# control_v1.net
KiCad netlist of a schematic drawn in EAGLE
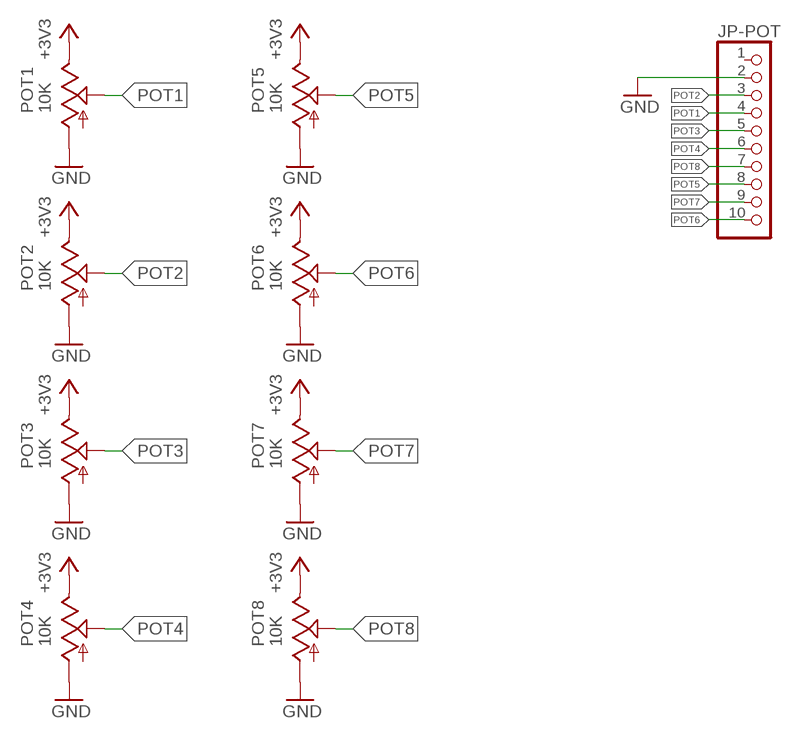
[diagram p0: schematic, sheet 1]
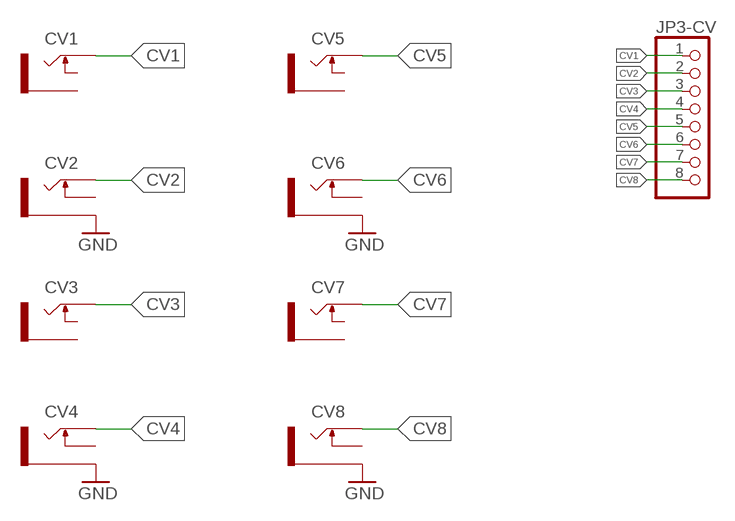
[diagram p1: schematic, sheet 2]
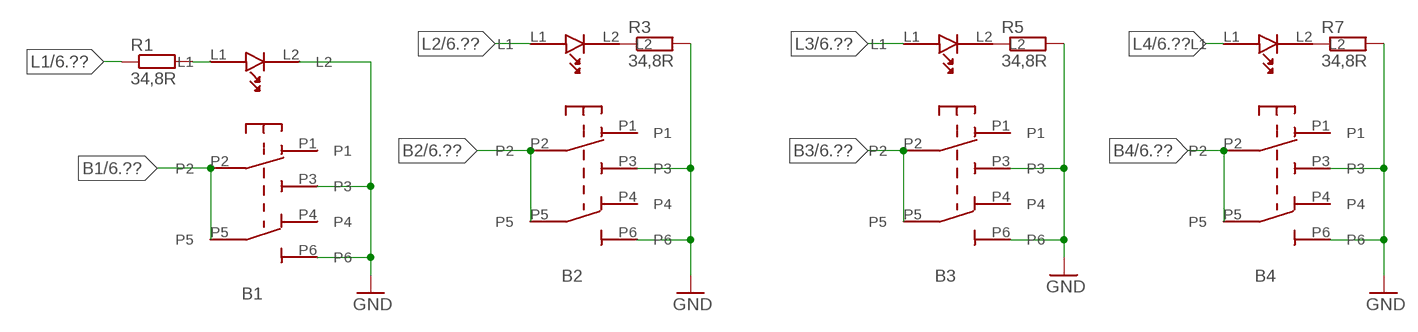
[diagram p2: schematic, sheet 3]
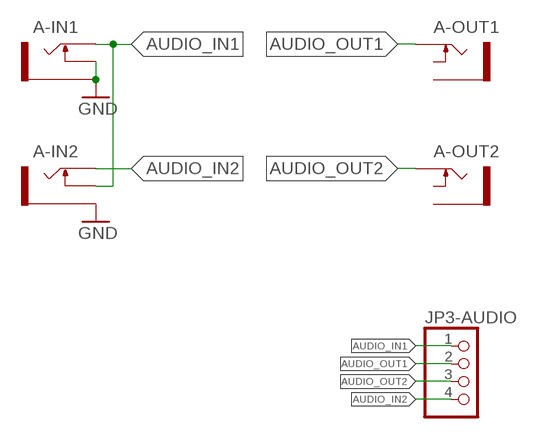
[diagram p3: schematic, sheet 4]
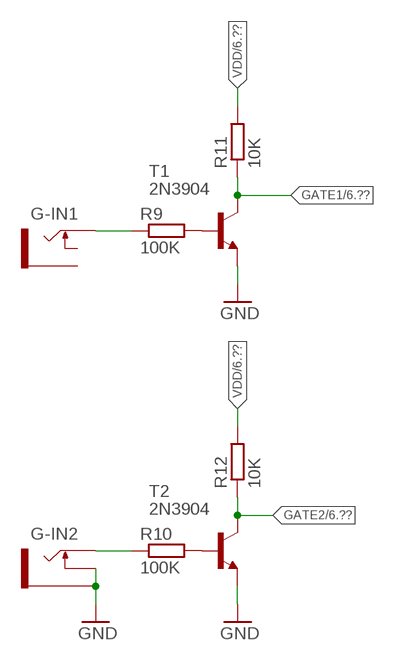
[diagram p4: schematic, sheet 5]
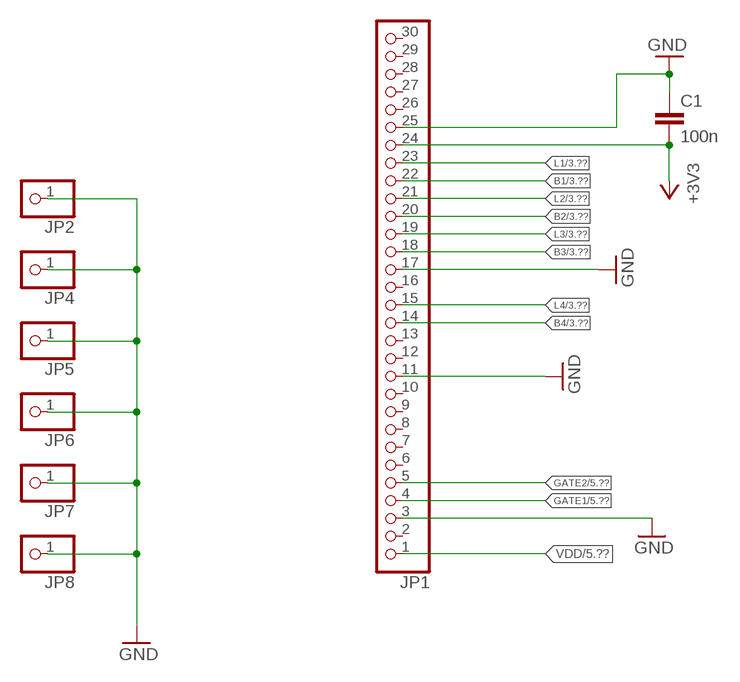
[diagram p5: schematic, sheet 6]

(export (version "E")
  (design (tool "Eeschema 10.0.6"))
  (components
    (comp (ref "JP-POT")
      (value "PINHD-1X10_2.54")
      (footprint "eagle-import:1X10")
      (libsource (lib "eagle-import") (part "PINHD-1X10_2.54"))
    )
    (comp (ref "POT1")
      (value "10K")
      (footprint "eagle-import:9MM_SNAP-IN_POT")
      (libsource (lib "eagle-import") (part "9MM_SNAP-IN_POT_"))
    )
    (comp (ref "POT2")
      (value "10K")
      (footprint "eagle-import:9MM_SNAP-IN_POT")
      (libsource (lib "eagle-import") (part "9MM_SNAP-IN_POT_"))
    )
    (comp (ref "POT3")
      (value "10K")
      (footprint "eagle-import:9MM_SNAP-IN_POT")
      (libsource (lib "eagle-import") (part "9MM_SNAP-IN_POT_"))
    )
    (comp (ref "POT4")
      (value "10K")
      (footprint "eagle-import:9MM_SNAP-IN_POT")
      (libsource (lib "eagle-import") (part "9MM_SNAP-IN_POT_"))
    )
    (comp (ref "POT5")
      (value "10K")
      (footprint "eagle-import:9MM_SNAP-IN_POT")
      (libsource (lib "eagle-import") (part "9MM_SNAP-IN_POT_"))
    )
    (comp (ref "POT6")
      (value "10K")
      (footprint "eagle-import:9MM_SNAP-IN_POT")
      (libsource (lib "eagle-import") (part "9MM_SNAP-IN_POT_"))
    )
    (comp (ref "POT7")
      (value "10K")
      (footprint "eagle-import:9MM_SNAP-IN_POT")
      (libsource (lib "eagle-import") (part "9MM_SNAP-IN_POT_"))
    )
    (comp (ref "POT8")
      (value "10K")
      (footprint "eagle-import:9MM_SNAP-IN_POT")
      (libsource (lib "eagle-import") (part "9MM_SNAP-IN_POT_"))
    )
    (comp (ref "A-IN1")
      (value "THONKICONNNEW")
      (footprint "eagle-import:WQP-PJ301M-12_JACK")
      (libsource (lib "eagle-import") (part "THONKICONNNEW"))
    )
    (comp (ref "A-IN2")
      (value "THONKICONNNEW")
      (footprint "eagle-import:WQP-PJ301M-12_JACK")
      (libsource (lib "eagle-import") (part "THONKICONNNEW"))
    )
    (comp (ref "A-OUT1")
      (value "THONKICONNNEW")
      (footprint "eagle-import:WQP-PJ301M-12_JACK")
      (libsource (lib "eagle-import") (part "MusicThingModular mod_THONKICONNNEW"))
    )
    (comp (ref "A-OUT2")
      (value "THONKICONNNEW")
      (footprint "eagle-import:WQP-PJ301M-12_JACK")
      (libsource (lib "eagle-import") (part "MusicThingModular mod_THONKICONNNEW"))
    )
    (comp (ref "JP3-AUDIO")
      (value "PINHD-1X4")
      (footprint "eagle-import:1X04")
      (libsource (lib "eagle-import") (part "PINHD-1X4"))
    )
    (comp (ref "C1")
      (value "100n")
      (footprint "eagle-import:C025-025X050")
      (libsource (lib "eagle-import") (part "C-EU025-025X050"))
    )
    (comp (ref "JP1")
      (value "PINHD-1X30")
      (footprint "eagle-import:1X30")
      (libsource (lib "eagle-import") (part "PINHD-1X30"))
    )
    (comp (ref "JP2")
      (value "PINHD-1X1")
      (footprint "eagle-import:1X01")
      (libsource (lib "eagle-import") (part "PINHD-1X1"))
    )
    (comp (ref "JP4")
      (value "PINHD-1X1")
      (footprint "eagle-import:1X01")
      (libsource (lib "eagle-import") (part "PINHD-1X1"))
    )
    (comp (ref "JP5")
      (value "PINHD-1X1")
      (footprint "eagle-import:1X01")
      (libsource (lib "eagle-import") (part "PINHD-1X1"))
    )
    (comp (ref "JP6")
      (value "PINHD-1X1")
      (footprint "eagle-import:1X01")
      (libsource (lib "eagle-import") (part "PINHD-1X1"))
    )
    (comp (ref "JP7")
      (value "PINHD-1X1")
      (footprint "eagle-import:1X01")
      (libsource (lib "eagle-import") (part "PINHD-1X1"))
    )
    (comp (ref "JP8")
      (value "PINHD-1X1")
      (footprint "eagle-import:1X01")
      (libsource (lib "eagle-import") (part "PINHD-1X1"))
    )
    (comp (ref "B1")
      (value "LP4OA1PBCTG")
      (footprint "eagle-import:LP4OA1PBCT")
      (libsource (lib "eagle-import") (part "LP4OA1PBCTG"))
    )
    (comp (ref "B2")
      (value "LP4OA1PBCTG")
      (footprint "eagle-import:LP4OA1PBCT")
      (libsource (lib "eagle-import") (part "LP4OA1PBCTG"))
    )
    (comp (ref "B3")
      (value "LP4OA1PBCTG")
      (footprint "eagle-import:LP4OA1PBCT")
      (libsource (lib "eagle-import") (part "LP4OA1PBCTG"))
    )
    (comp (ref "B4")
      (value "LP4OA1PBCTG")
      (footprint "eagle-import:LP4OA1PBCT")
      (libsource (lib "eagle-import") (part "LP4OA1PBCTG"))
    )
    (comp (ref "R1")
      (value "34,8R")
      (footprint "eagle-import:0207_7")
      (libsource (lib "eagle-import") (part "R-EU_0207/7"))
    )
    (comp (ref "R3")
      (value "34,8R")
      (footprint "eagle-import:0207_7")
      (libsource (lib "eagle-import") (part "R-EU_0207/7"))
    )
    (comp (ref "R5")
      (value "34,8R")
      (footprint "eagle-import:0207_7")
      (libsource (lib "eagle-import") (part "R-EU_0207/7"))
    )
    (comp (ref "R7")
      (value "34,8R")
      (footprint "eagle-import:0207_7")
      (libsource (lib "eagle-import") (part "R-EU_0207/7"))
    )
    (comp (ref "CV1")
      (value "THONKICONNNEW")
      (footprint "eagle-import:WQP-PJ301M-12_JACK")
      (libsource (lib "eagle-import") (part "MusicThingModular mod_THONKICONNNEW"))
    )
    (comp (ref "CV2")
      (value "THONKICONNNEW")
      (footprint "eagle-import:WQP-PJ301M-12_JACK")
      (libsource (lib "eagle-import") (part "THONKICONNNEW"))
    )
    (comp (ref "CV3")
      (value "THONKICONNNEW")
      (footprint "eagle-import:WQP-PJ301M-12_JACK")
      (libsource (lib "eagle-import") (part "MusicThingModular mod_THONKICONNNEW"))
    )
    (comp (ref "CV4")
      (value "THONKICONNNEW")
      (footprint "eagle-import:WQP-PJ301M-12_JACK")
      (libsource (lib "eagle-import") (part "THONKICONNNEW"))
    )
    (comp (ref "CV5")
      (value "THONKICONNNEW")
      (footprint "eagle-import:WQP-PJ301M-12_JACK")
      (libsource (lib "eagle-import") (part "MusicThingModular mod_THONKICONNNEW"))
    )
    (comp (ref "CV6")
      (value "THONKICONNNEW")
      (footprint "eagle-import:WQP-PJ301M-12_JACK")
      (libsource (lib "eagle-import") (part "THONKICONNNEW"))
    )
    (comp (ref "CV7")
      (value "THONKICONNNEW")
      (footprint "eagle-import:WQP-PJ301M-12_JACK")
      (libsource (lib "eagle-import") (part "MusicThingModular mod_THONKICONNNEW"))
    )
    (comp (ref "CV8")
      (value "THONKICONNNEW")
      (footprint "eagle-import:WQP-PJ301M-12_JACK")
      (libsource (lib "eagle-import") (part "THONKICONNNEW"))
    )
    (comp (ref "JP3-CV")
      (value "PINHD-1X8")
      (footprint "eagle-import:1X08")
      (libsource (lib "eagle-import") (part "PINHD-1X8"))
    )
    (comp (ref "G-IN1")
      (value "THONKICONNNEW")
      (footprint "eagle-import:WQP-PJ301M-12_JACK")
      (libsource (lib "eagle-import") (part "MusicThingModular mod_THONKICONNNEW"))
    )
    (comp (ref "G-IN2")
      (value "THONKICONNNEW")
      (footprint "eagle-import:WQP-PJ301M-12_JACK")
      (libsource (lib "eagle-import") (part "THONKICONNNEW"))
    )
    (comp (ref "R9")
      (value "100K")
      (footprint "eagle-import:0207_7")
      (libsource (lib "eagle-import") (part "R-EU_0207/7"))
    )
    (comp (ref "R10")
      (value "100K")
      (footprint "eagle-import:0207_7")
      (libsource (lib "eagle-import") (part "R-EU_0207/7"))
    )
    (comp (ref "R11")
      (value "10K")
      (footprint "eagle-import:0207_7")
      (libsource (lib "eagle-import") (part "R-EU_0207/7"))
    )
    (comp (ref "R12")
      (value "10K")
      (footprint "eagle-import:0207_7")
      (libsource (lib "eagle-import") (part "R-EU_0207/7"))
    )
    (comp (ref "T1")
      (value "2N3904")
      (footprint "eagle-import:TO92")
      (libsource (lib "eagle-import") (part "2N3904"))
    )
    (comp (ref "T2")
      (value "2N3904")
      (footprint "eagle-import:TO92")
      (libsource (lib "eagle-import") (part "2N3904"))
    )
  )
  (nets
    (net (code "1") (name "+3V3") (class "Default")
      (node (ref "C1") (pin "2") (pinfunction "2_2") (pintype "passive"))
      (node (ref "JP1") (pin "24") (pinfunction "24_24") (pintype "passive"))
      (node (ref "POT1") (pin "3") (pinfunction "E_3") (pintype "passive"))
      (node (ref "POT2") (pin "3") (pinfunction "E_3") (pintype "passive"))
      (node (ref "POT3") (pin "3") (pinfunction "E_3") (pintype "passive"))
      (node (ref "POT4") (pin "3") (pinfunction "E_3") (pintype "passive"))
      (node (ref "POT5") (pin "3") (pinfunction "E_3") (pintype "passive"))
      (node (ref "POT6") (pin "3") (pinfunction "E_3") (pintype "passive"))
      (node (ref "POT7") (pin "3") (pinfunction "E_3") (pintype "passive"))
      (node (ref "POT8") (pin "3") (pinfunction "E_3") (pintype "passive"))
    )
    (net (code "2") (name "AUDIO_IN1") (class "Default")
      (node (ref "A-IN1") (pin "P$1_TIP") (pinfunction "TIP_P$1_TIP") (pintype "passive"))
      (node (ref "A-IN2") (pin "P$2_SWITCH") (pinfunction "SWITCH_P$2_SWITCH") (pintype "passive"))
      (node (ref "JP3-AUDIO") (pin "1") (pinfunction "1_1") (pintype "passive"))
    )
    (net (code "3") (name "AUDIO_IN2") (class "Default")
      (node (ref "A-IN2") (pin "P$1_TIP") (pinfunction "TIP_P$1_TIP") (pintype "passive"))
      (node (ref "JP3-AUDIO") (pin "4") (pinfunction "4_4") (pintype "passive"))
    )
    (net (code "4") (name "AUDIO_OUT1") (class "Default")
      (node (ref "A-OUT1") (pin "P$1_TIP") (pinfunction "TIP_P$1_TIP") (pintype "passive"))
      (node (ref "JP3-AUDIO") (pin "2") (pinfunction "2_2") (pintype "passive"))
    )
    (net (code "5") (name "AUDIO_OUT2") (class "Default")
      (node (ref "A-OUT2") (pin "P$1_TIP") (pinfunction "TIP_P$1_TIP") (pintype "passive"))
      (node (ref "JP3-AUDIO") (pin "3") (pinfunction "3_3") (pintype "passive"))
    )
    (net (code "6") (name "B1") (class "Default")
      (node (ref "B1") (pin "P2") (pinfunction "P2_P2") (pintype "bidirectional"))
      (node (ref "B1") (pin "P5") (pinfunction "P5_P5") (pintype "bidirectional"))
      (node (ref "JP1") (pin "22") (pinfunction "22_22") (pintype "passive"))
    )
    (net (code "7") (name "B2") (class "Default")
      (node (ref "B2") (pin "P2") (pinfunction "P2_P2") (pintype "bidirectional"))
      (node (ref "B2") (pin "P5") (pinfunction "P5_P5") (pintype "bidirectional"))
      (node (ref "JP1") (pin "20") (pinfunction "20_20") (pintype "passive"))
    )
    (net (code "8") (name "B3") (class "Default")
      (node (ref "B3") (pin "P2") (pinfunction "P2_P2") (pintype "bidirectional"))
      (node (ref "B3") (pin "P5") (pinfunction "P5_P5") (pintype "bidirectional"))
      (node (ref "JP1") (pin "18") (pinfunction "18_18") (pintype "passive"))
    )
    (net (code "9") (name "B4") (class "Default")
      (node (ref "B4") (pin "P2") (pinfunction "P2_P2") (pintype "bidirectional"))
      (node (ref "B4") (pin "P5") (pinfunction "P5_P5") (pintype "bidirectional"))
      (node (ref "JP1") (pin "14") (pinfunction "14_14") (pintype "passive"))
    )
    (net (code "10") (name "CV1") (class "Default")
      (node (ref "CV1") (pin "P$1_TIP") (pinfunction "TIP_P$1_TIP") (pintype "passive"))
      (node (ref "JP3-CV") (pin "1") (pinfunction "1_1") (pintype "passive"))
    )
    (net (code "11") (name "CV2") (class "Default")
      (node (ref "CV2") (pin "P$1_TIP") (pinfunction "TIP_P$1_TIP") (pintype "passive"))
      (node (ref "JP3-CV") (pin "2") (pinfunction "2_2") (pintype "passive"))
    )
    (net (code "12") (name "CV3") (class "Default")
      (node (ref "CV3") (pin "P$1_TIP") (pinfunction "TIP_P$1_TIP") (pintype "passive"))
      (node (ref "JP3-CV") (pin "3") (pinfunction "3_3") (pintype "passive"))
    )
    (net (code "13") (name "CV4") (class "Default")
      (node (ref "CV4") (pin "P$1_TIP") (pinfunction "TIP_P$1_TIP") (pintype "passive"))
      (node (ref "JP3-CV") (pin "4") (pinfunction "4_4") (pintype "passive"))
    )
    (net (code "14") (name "CV5") (class "Default")
      (node (ref "CV5") (pin "P$1_TIP") (pinfunction "TIP_P$1_TIP") (pintype "passive"))
      (node (ref "JP3-CV") (pin "5") (pinfunction "5_5") (pintype "passive"))
    )
    (net (code "15") (name "CV6") (class "Default")
      (node (ref "CV6") (pin "P$1_TIP") (pinfunction "TIP_P$1_TIP") (pintype "passive"))
      (node (ref "JP3-CV") (pin "6") (pinfunction "6_6") (pintype "passive"))
    )
    (net (code "16") (name "CV7") (class "Default")
      (node (ref "CV7") (pin "P$1_TIP") (pinfunction "TIP_P$1_TIP") (pintype "passive"))
      (node (ref "JP3-CV") (pin "7") (pinfunction "7_7") (pintype "passive"))
    )
    (net (code "17") (name "CV8") (class "Default")
      (node (ref "CV8") (pin "P$1_TIP") (pinfunction "TIP_P$1_TIP") (pintype "passive"))
      (node (ref "JP3-CV") (pin "8") (pinfunction "8_8") (pintype "passive"))
    )
    (net (code "18") (name "GATE1") (class "Default")
      (node (ref "JP1") (pin "4") (pinfunction "4_4") (pintype "passive"))
      (node (ref "R11") (pin "1") (pinfunction "1_1") (pintype "passive"))
      (node (ref "T1") (pin "1") (pinfunction "C_1") (pintype "passive"))
    )
    (net (code "19") (name "GATE2") (class "Default")
      (node (ref "JP1") (pin "5") (pinfunction "5_5") (pintype "passive"))
      (node (ref "R12") (pin "1") (pinfunction "1_1") (pintype "passive"))
      (node (ref "T2") (pin "1") (pinfunction "C_1") (pintype "passive"))
    )
    (net (code "20") (name "GND") (class "Default")
      (node (ref "A-IN1") (pin "P$2_SWITCH") (pinfunction "SWITCH_P$2_SWITCH") (pintype "passive"))
      (node (ref "A-IN1") (pin "P$3_SLEEVE") (pinfunction "SLEEVE_P$3_SLEEVE") (pintype "passive"))
      (node (ref "A-IN2") (pin "P$3_SLEEVE") (pinfunction "SLEEVE_P$3_SLEEVE") (pintype "passive"))
      (node (ref "B1") (pin "L2") (pinfunction "L2_L2") (pintype "output"))
      (node (ref "B1") (pin "P3") (pinfunction "P3_P3") (pintype "bidirectional"))
      (node (ref "B1") (pin "P6") (pinfunction "P6_P6") (pintype "bidirectional"))
      (node (ref "B2") (pin "P3") (pinfunction "P3_P3") (pintype "bidirectional"))
      (node (ref "B2") (pin "P6") (pinfunction "P6_P6") (pintype "bidirectional"))
      (node (ref "B3") (pin "P3") (pinfunction "P3_P3") (pintype "bidirectional"))
      (node (ref "B3") (pin "P6") (pinfunction "P6_P6") (pintype "bidirectional"))
      (node (ref "B4") (pin "P3") (pinfunction "P3_P3") (pintype "bidirectional"))
      (node (ref "B4") (pin "P6") (pinfunction "P6_P6") (pintype "bidirectional"))
      (node (ref "C1") (pin "1") (pinfunction "1_1") (pintype "passive"))
      (node (ref "CV2") (pin "P$3_SLEEVE") (pinfunction "SLEEVE_P$3_SLEEVE") (pintype "passive"))
      (node (ref "CV4") (pin "P$3_SLEEVE") (pinfunction "SLEEVE_P$3_SLEEVE") (pintype "passive"))
      (node (ref "CV6") (pin "P$3_SLEEVE") (pinfunction "SLEEVE_P$3_SLEEVE") (pintype "passive"))
      (node (ref "CV8") (pin "P$3_SLEEVE") (pinfunction "SLEEVE_P$3_SLEEVE") (pintype "passive"))
      (node (ref "G-IN2") (pin "P$2_SWITCH") (pinfunction "SWITCH_P$2_SWITCH") (pintype "passive"))
      (node (ref "G-IN2") (pin "P$3_SLEEVE") (pinfunction "SLEEVE_P$3_SLEEVE") (pintype "passive"))
      (node (ref "JP-POT") (pin "2") (pinfunction "2_2") (pintype "passive"))
      (node (ref "JP1") (pin "11") (pinfunction "11_11") (pintype "passive"))
      (node (ref "JP1") (pin "17") (pinfunction "17_17") (pintype "passive"))
      (node (ref "JP1") (pin "25") (pinfunction "25_25") (pintype "passive"))
      (node (ref "JP1") (pin "3") (pinfunction "3_3") (pintype "passive"))
      (node (ref "JP2") (pin "1") (pinfunction "1_1") (pintype "passive"))
      (node (ref "JP4") (pin "1") (pinfunction "1_1") (pintype "passive"))
      (node (ref "JP5") (pin "1") (pinfunction "1_1") (pintype "passive"))
      (node (ref "JP6") (pin "1") (pinfunction "1_1") (pintype "passive"))
      (node (ref "JP7") (pin "1") (pinfunction "1_1") (pintype "passive"))
      (node (ref "JP8") (pin "1") (pinfunction "1_1") (pintype "passive"))
      (node (ref "POT1") (pin "1") (pinfunction "A_1") (pintype "passive"))
      (node (ref "POT2") (pin "1") (pinfunction "A_1") (pintype "passive"))
      (node (ref "POT3") (pin "1") (pinfunction "A_1") (pintype "passive"))
      (node (ref "POT4") (pin "1") (pinfunction "A_1") (pintype "passive"))
      (node (ref "POT5") (pin "1") (pinfunction "A_1") (pintype "passive"))
      (node (ref "POT6") (pin "1") (pinfunction "A_1") (pintype "passive"))
      (node (ref "POT7") (pin "1") (pinfunction "A_1") (pintype "passive"))
      (node (ref "POT8") (pin "1") (pinfunction "A_1") (pintype "passive"))
      (node (ref "R3") (pin "2") (pinfunction "2_2") (pintype "passive"))
      (node (ref "R5") (pin "2") (pinfunction "2_2") (pintype "passive"))
      (node (ref "R7") (pin "2") (pinfunction "2_2") (pintype "passive"))
      (node (ref "T1") (pin "3") (pinfunction "E_3") (pintype "passive"))
      (node (ref "T2") (pin "3") (pinfunction "E_3") (pintype "passive"))
    )
    (net (code "21") (name "L1") (class "Default")
      (node (ref "JP1") (pin "23") (pinfunction "23_23") (pintype "passive"))
      (node (ref "R1") (pin "1") (pinfunction "1_1") (pintype "passive"))
    )
    (net (code "22") (name "L2") (class "Default")
      (node (ref "B2") (pin "L1") (pinfunction "L1_L1") (pintype "input"))
      (node (ref "JP1") (pin "21") (pinfunction "21_21") (pintype "passive"))
    )
    (net (code "23") (name "L3") (class "Default")
      (node (ref "B3") (pin "L1") (pinfunction "L1_L1") (pintype "input"))
      (node (ref "JP1") (pin "19") (pinfunction "19_19") (pintype "passive"))
    )
    (net (code "24") (name "L4") (class "Default")
      (node (ref "B4") (pin "L1") (pinfunction "L1_L1") (pintype "input"))
      (node (ref "JP1") (pin "15") (pinfunction "15_15") (pintype "passive"))
    )
    (net (code "25") (name "Net-(B1-PadL1)") (class "Default")
      (node (ref "B1") (pin "L1") (pinfunction "L1_L1") (pintype "input"))
      (node (ref "R1") (pin "2") (pinfunction "2_2") (pintype "passive"))
    )
    (net (code "26") (name "Net-(B2-PadL2)") (class "Default")
      (node (ref "B2") (pin "L2") (pinfunction "L2_L2") (pintype "output"))
      (node (ref "R3") (pin "1") (pinfunction "1_1") (pintype "passive"))
    )
    (net (code "27") (name "Net-(B3-PadL2)") (class "Default")
      (node (ref "B3") (pin "L2") (pinfunction "L2_L2") (pintype "output"))
      (node (ref "R5") (pin "1") (pinfunction "1_1") (pintype "passive"))
    )
    (net (code "28") (name "Net-(B4-PadL2)") (class "Default")
      (node (ref "B4") (pin "L2") (pinfunction "L2_L2") (pintype "output"))
      (node (ref "R7") (pin "1") (pinfunction "1_1") (pintype "passive"))
    )
    (net (code "29") (name "Net-(G-IN1-TIP)") (class "Default")
      (node (ref "G-IN1") (pin "P$1_TIP") (pinfunction "TIP_P$1_TIP") (pintype "passive"))
      (node (ref "R9") (pin "1") (pinfunction "1_1") (pintype "passive"))
    )
    (net (code "30") (name "Net-(G-IN2-TIP)") (class "Default")
      (node (ref "G-IN2") (pin "P$1_TIP") (pinfunction "TIP_P$1_TIP") (pintype "passive"))
      (node (ref "R10") (pin "1") (pinfunction "1_1") (pintype "passive"))
    )
    (net (code "31") (name "Net-(T1-B)") (class "Default")
      (node (ref "R9") (pin "2") (pinfunction "2_2") (pintype "passive"))
      (node (ref "T1") (pin "2") (pinfunction "B_2") (pintype "passive"))
    )
    (net (code "32") (name "Net-(T2-B)") (class "Default")
      (node (ref "R10") (pin "2") (pinfunction "2_2") (pintype "passive"))
      (node (ref "T2") (pin "2") (pinfunction "B_2") (pintype "passive"))
    )
    (net (code "33") (name "POT1") (class "Default")
      (node (ref "JP-POT") (pin "4") (pinfunction "4_4") (pintype "passive"))
      (node (ref "POT1") (pin "2") (pinfunction "S_2") (pintype "passive"))
    )
    (net (code "34") (name "POT2") (class "Default")
      (node (ref "JP-POT") (pin "3") (pinfunction "3_3") (pintype "passive"))
      (node (ref "POT2") (pin "2") (pinfunction "S_2") (pintype "passive"))
    )
    (net (code "35") (name "POT3") (class "Default")
      (node (ref "JP-POT") (pin "5") (pinfunction "5_5") (pintype "passive"))
      (node (ref "POT3") (pin "2") (pinfunction "S_2") (pintype "passive"))
    )
    (net (code "36") (name "POT4") (class "Default")
      (node (ref "JP-POT") (pin "6") (pinfunction "6_6") (pintype "passive"))
      (node (ref "POT4") (pin "2") (pinfunction "S_2") (pintype "passive"))
    )
    (net (code "37") (name "POT5") (class "Default")
      (node (ref "JP-POT") (pin "8") (pinfunction "8_8") (pintype "passive"))
      (node (ref "POT5") (pin "2") (pinfunction "S_2") (pintype "passive"))
    )
    (net (code "38") (name "POT6") (class "Default")
      (node (ref "JP-POT") (pin "10") (pinfunction "10_10") (pintype "passive"))
      (node (ref "POT6") (pin "2") (pinfunction "S_2") (pintype "passive"))
    )
    (net (code "39") (name "POT7") (class "Default")
      (node (ref "JP-POT") (pin "9") (pinfunction "9_9") (pintype "passive"))
      (node (ref "POT7") (pin "2") (pinfunction "S_2") (pintype "passive"))
    )
    (net (code "40") (name "POT8") (class "Default")
      (node (ref "JP-POT") (pin "7") (pinfunction "7_7") (pintype "passive"))
      (node (ref "POT8") (pin "2") (pinfunction "S_2") (pintype "passive"))
    )
    (net (code "41") (name "VDD") (class "Default")
      (node (ref "JP1") (pin "1") (pinfunction "1_1") (pintype "passive"))
      (node (ref "R11") (pin "2") (pinfunction "2_2") (pintype "passive"))
      (node (ref "R12") (pin "2") (pinfunction "2_2") (pintype "passive"))
    )
    (net (code "42") (name "unconnected-(B1-PadP1)") (class "Default")
      (node (ref "B1") (pin "P1") (pinfunction "P1_P1") (pintype "bidirectional"))
    )
    (net (code "43") (name "unconnected-(B1-PadP4)") (class "Default")
      (node (ref "B1") (pin "P4") (pinfunction "P4_P4") (pintype "bidirectional"))
    )
    (net (code "44") (name "unconnected-(B2-PadP1)") (class "Default")
      (node (ref "B2") (pin "P1") (pinfunction "P1_P1") (pintype "bidirectional"))
    )
    (net (code "45") (name "unconnected-(B2-PadP4)") (class "Default")
      (node (ref "B2") (pin "P4") (pinfunction "P4_P4") (pintype "bidirectional"))
    )
    (net (code "46") (name "unconnected-(B3-PadP1)") (class "Default")
      (node (ref "B3") (pin "P1") (pinfunction "P1_P1") (pintype "bidirectional"))
    )
    (net (code "47") (name "unconnected-(B3-PadP4)") (class "Default")
      (node (ref "B3") (pin "P4") (pinfunction "P4_P4") (pintype "bidirectional"))
    )
    (net (code "48") (name "unconnected-(B4-PadP1)") (class "Default")
      (node (ref "B4") (pin "P1") (pinfunction "P1_P1") (pintype "bidirectional"))
    )
    (net (code "49") (name "unconnected-(B4-PadP4)") (class "Default")
      (node (ref "B4") (pin "P4") (pinfunction "P4_P4") (pintype "bidirectional"))
    )
    (net (code "50") (name "unconnected-(CV2-SWITCH-PadP$2_SWITCH)") (class "Default")
      (node (ref "CV2") (pin "P$2_SWITCH") (pinfunction "SWITCH_P$2_SWITCH") (pintype "passive"))
    )
    (net (code "51") (name "unconnected-(CV4-SWITCH-PadP$2_SWITCH)") (class "Default")
      (node (ref "CV4") (pin "P$2_SWITCH") (pinfunction "SWITCH_P$2_SWITCH") (pintype "passive"))
    )
    (net (code "52") (name "unconnected-(CV6-SWITCH-PadP$2_SWITCH)") (class "Default")
      (node (ref "CV6") (pin "P$2_SWITCH") (pinfunction "SWITCH_P$2_SWITCH") (pintype "passive"))
    )
    (net (code "53") (name "unconnected-(CV8-SWITCH-PadP$2_SWITCH)") (class "Default")
      (node (ref "CV8") (pin "P$2_SWITCH") (pinfunction "SWITCH_P$2_SWITCH") (pintype "passive"))
    )
    (net (code "54") (name "unconnected-(JP-POT-Pad1)") (class "Default")
      (node (ref "JP-POT") (pin "1") (pinfunction "1_1") (pintype "passive"))
    )
    (net (code "55") (name "unconnected-(JP1-Pad2)") (class "Default")
      (node (ref "JP1") (pin "2") (pinfunction "2_2") (pintype "passive"))
    )
    (net (code "56") (name "unconnected-(JP1-Pad6)") (class "Default")
      (node (ref "JP1") (pin "6") (pinfunction "6_6") (pintype "passive"))
    )
    (net (code "57") (name "unconnected-(JP1-Pad7)") (class "Default")
      (node (ref "JP1") (pin "7") (pinfunction "7_7") (pintype "passive"))
    )
    (net (code "58") (name "unconnected-(JP1-Pad8)") (class "Default")
      (node (ref "JP1") (pin "8") (pinfunction "8_8") (pintype "passive"))
    )
    (net (code "59") (name "unconnected-(JP1-Pad9)") (class "Default")
      (node (ref "JP1") (pin "9") (pinfunction "9_9") (pintype "passive"))
    )
    (net (code "60") (name "unconnected-(JP1-Pad10)") (class "Default")
      (node (ref "JP1") (pin "10") (pinfunction "10_10") (pintype "passive"))
    )
    (net (code "61") (name "unconnected-(JP1-Pad12)") (class "Default")
      (node (ref "JP1") (pin "12") (pinfunction "12_12") (pintype "passive"))
    )
    (net (code "62") (name "unconnected-(JP1-Pad13)") (class "Default")
      (node (ref "JP1") (pin "13") (pinfunction "13_13") (pintype "passive"))
    )
    (net (code "63") (name "unconnected-(JP1-Pad16)") (class "Default")
      (node (ref "JP1") (pin "16") (pinfunction "16_16") (pintype "passive"))
    )
    (net (code "64") (name "unconnected-(JP1-Pad26)") (class "Default")
      (node (ref "JP1") (pin "26") (pinfunction "26_26") (pintype "passive"))
    )
    (net (code "65") (name "unconnected-(JP1-Pad27)") (class "Default")
      (node (ref "JP1") (pin "27") (pinfunction "27_27") (pintype "passive"))
    )
    (net (code "66") (name "unconnected-(JP1-Pad28)") (class "Default")
      (node (ref "JP1") (pin "28") (pinfunction "28_28") (pintype "passive"))
    )
    (net (code "67") (name "unconnected-(JP1-Pad29)") (class "Default")
      (node (ref "JP1") (pin "29") (pinfunction "29_29") (pintype "passive"))
    )
    (net (code "68") (name "unconnected-(JP1-Pad30)") (class "Default")
      (node (ref "JP1") (pin "30") (pinfunction "30_30") (pintype "passive"))
    )
  )
)
